# Power_Supply_Board.net
KiCad netlist of a schematic drawn in EAGLE
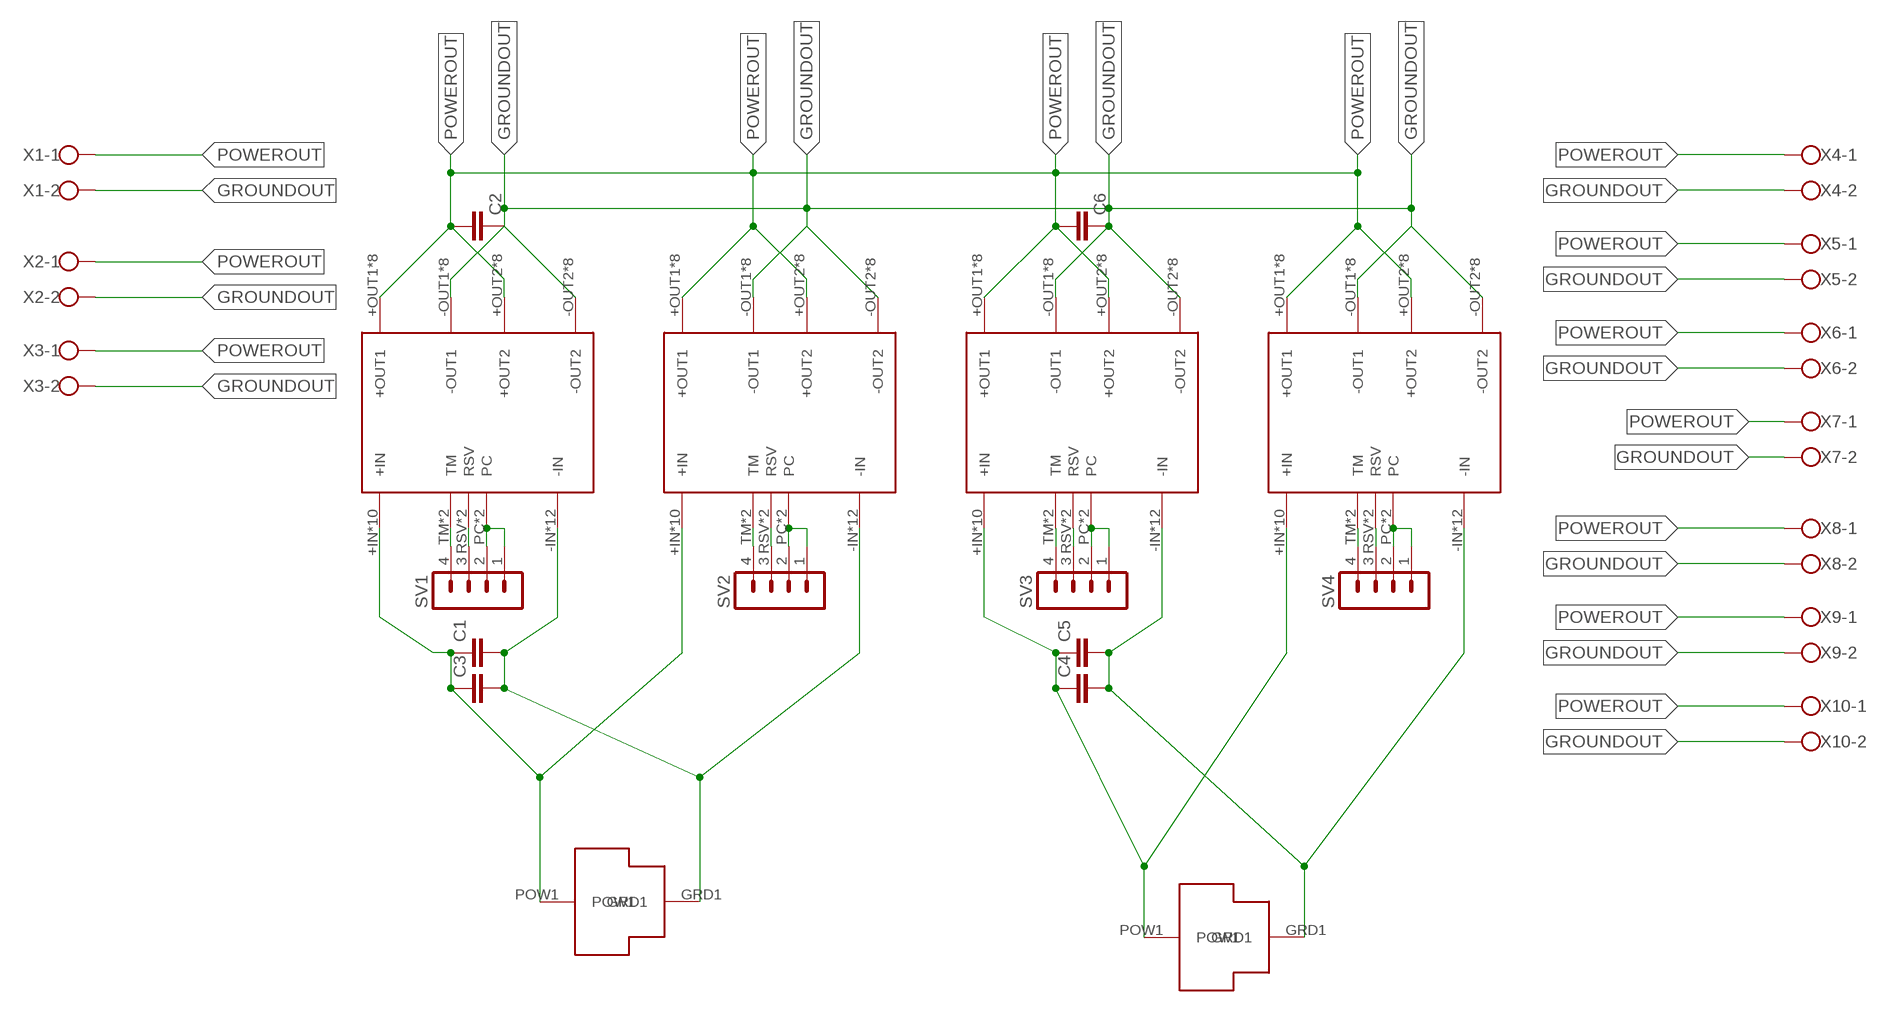
[diagram p0: schematic, sheet 1]

(export (version "E")
  (design (tool "Eeschema 10.0.6"))
  (components
    (comp (ref "C1")
      (value "C2,5-3")
      (footprint "eagle-import:C2.5-3")
      (libsource (lib "eagle-import") (part "C2,5-3"))
    )
    (comp (ref "C2")
      (value "C2,5-3")
      (footprint "eagle-import:C2.5-3")
      (libsource (lib "eagle-import") (part "C2,5-3"))
    )
    (comp (ref "C3")
      (value "C2,5-3")
      (footprint "eagle-import:C2.5-3")
      (libsource (lib "eagle-import") (part "C2,5-3"))
    )
    (comp (ref "C4")
      (value "C2,5-3")
      (footprint "eagle-import:C2.5-3")
      (libsource (lib "eagle-import") (part "C2,5-3"))
    )
    (comp (ref "C5")
      (value "C2,5-3")
      (footprint "eagle-import:C2.5-3")
      (libsource (lib "eagle-import") (part "C2,5-3"))
    )
    (comp (ref "C6")
      (value "C2,5-3")
      (footprint "eagle-import:C2.5-3")
      (libsource (lib "eagle-import") (part "C2,5-3"))
    )
    (comp (ref "SV1")
      (value "MA04-1")
      (footprint "eagle-import:MA04-1")
      (libsource (lib "eagle-import") (part "MA04-1"))
    )
    (comp (ref "SV2")
      (value "MA04-1")
      (footprint "eagle-import:MA04-1")
      (libsource (lib "eagle-import") (part "MA04-1"))
    )
    (comp (ref "SV3")
      (value "MA04-1")
      (footprint "eagle-import:MA04-1")
      (libsource (lib "eagle-import") (part "MA04-1"))
    )
    (comp (ref "SV4")
      (value "MA04-1")
      (footprint "eagle-import:MA04-1")
      (libsource (lib "eagle-import") (part "MA04-1"))
    )
    (comp (ref "U$3")
      (value "MOLEXMEGAFIT")
      (footprint "eagle-import:MOLEXMEGAFIT")
      (libsource (lib "eagle-import") (part "MOLEXMEGAFIT"))
    )
    (comp (ref "U$9")
      (value "MOLEXMEGAFIT")
      (footprint "eagle-import:MOLEXMEGAFIT")
      (libsource (lib "eagle-import") (part "MOLEXMEGAFIT"))
    )
    (comp (ref "VC1")
      (value "VOLTAGECONVERTER")
      (footprint "eagle-import:VOLTAGECONVERTER")
      (libsource (lib "eagle-import") (part "VOLTAGECONVERTER"))
    )
    (comp (ref "VC2")
      (value "VOLTAGECONVERTER")
      (footprint "eagle-import:VOLTAGECONVERTER")
      (libsource (lib "eagle-import") (part "VOLTAGECONVERTER"))
    )
    (comp (ref "VC3")
      (value "VOLTAGECONVERTER")
      (footprint "eagle-import:VOLTAGECONVERTER")
      (libsource (lib "eagle-import") (part "VOLTAGECONVERTER"))
    )
    (comp (ref "VC4")
      (value "VOLTAGECONVERTER")
      (footprint "eagle-import:VOLTAGECONVERTER")
      (libsource (lib "eagle-import") (part "VOLTAGECONVERTER"))
    )
    (comp (ref "X1")
      (value "W237-102")
      (footprint "eagle-import:W237-102")
      (fields (field (name "MPN") "237-102"))
      (libsource (lib "eagle-import") (part "W237-102"))
    )
    (comp (ref "X2")
      (value "W237-102")
      (footprint "eagle-import:W237-102")
      (fields (field (name "MPN") "237-102"))
      (libsource (lib "eagle-import") (part "W237-102"))
    )
    (comp (ref "X3")
      (value "W237-102")
      (footprint "eagle-import:W237-102")
      (fields (field (name "MPN") "237-102"))
      (libsource (lib "eagle-import") (part "W237-102"))
    )
    (comp (ref "X4")
      (value "W237-102")
      (footprint "eagle-import:W237-102")
      (fields (field (name "MPN") "237-102"))
      (libsource (lib "eagle-import") (part "W237-102"))
    )
    (comp (ref "X5")
      (value "W237-102")
      (footprint "eagle-import:W237-102")
      (fields (field (name "MPN") "237-102"))
      (libsource (lib "eagle-import") (part "W237-102"))
    )
    (comp (ref "X6")
      (value "W237-102")
      (footprint "eagle-import:W237-102")
      (fields (field (name "MPN") "237-102"))
      (libsource (lib "eagle-import") (part "W237-102"))
    )
    (comp (ref "X7")
      (value "W237-102")
      (footprint "eagle-import:W237-102")
      (fields (field (name "MPN") "237-102"))
      (libsource (lib "eagle-import") (part "W237-102"))
    )
    (comp (ref "X8")
      (value "W237-102")
      (footprint "eagle-import:W237-102")
      (fields (field (name "MPN") "237-102"))
      (libsource (lib "eagle-import") (part "W237-102"))
    )
    (comp (ref "X9")
      (value "W237-102")
      (footprint "eagle-import:W237-102")
      (fields (field (name "MPN") "237-102"))
      (libsource (lib "eagle-import") (part "W237-102"))
    )
    (comp (ref "X10")
      (value "W237-102")
      (footprint "eagle-import:W237-102")
      (fields (field (name "MPN") "237-102"))
      (libsource (lib "eagle-import") (part "W237-102"))
    )
  )
  (nets
    (net (code "1") (name "/GROUNDIN") (class "Default")
      (node (ref "C1") (pin "2") (pinfunction "2_2") (pintype "passive"))
      (node (ref "C3") (pin "2") (pinfunction "2_2") (pintype "passive"))
      (node (ref "C4") (pin "2") (pinfunction "2_2") (pintype "passive"))
      (node (ref "C5") (pin "2") (pinfunction "2_2") (pintype "passive"))
      (node (ref "U$3") (pin "GRD1") (pinfunction "GRD1_GRD1") (pintype "bidirectional"))
      (node (ref "U$9") (pin "GRD1") (pinfunction "GRD1_GRD1") (pintype "bidirectional"))
      (node (ref "VC1") (pin "-IN") (pinfunction "-IN_-IN") (pintype "bidirectional"))
      (node (ref "VC1") (pin "-IN@0") (pinfunction "-IN_-IN@0") (pintype "bidirectional"))
      (node (ref "VC1") (pin "-IN@1") (pinfunction "-IN_-IN@1") (pintype "bidirectional"))
      (node (ref "VC1") (pin "-IN@10") (pinfunction "-IN_-IN@10") (pintype "bidirectional"))
      (node (ref "VC1") (pin "-IN@2") (pinfunction "-IN_-IN@2") (pintype "bidirectional"))
      (node (ref "VC1") (pin "-IN@3") (pinfunction "-IN_-IN@3") (pintype "bidirectional"))
      (node (ref "VC1") (pin "-IN@4") (pinfunction "-IN_-IN@4") (pintype "bidirectional"))
      (node (ref "VC1") (pin "-IN@5") (pinfunction "-IN_-IN@5") (pintype "bidirectional"))
      (node (ref "VC1") (pin "-IN@6") (pinfunction "-IN_-IN@6") (pintype "bidirectional"))
      (node (ref "VC1") (pin "-IN@7") (pinfunction "-IN_-IN@7") (pintype "bidirectional"))
      (node (ref "VC1") (pin "-IN@8") (pinfunction "-IN_-IN@8") (pintype "bidirectional"))
      (node (ref "VC1") (pin "-IN@9") (pinfunction "-IN_-IN@9") (pintype "bidirectional"))
      (node (ref "VC2") (pin "-IN") (pinfunction "-IN_-IN") (pintype "bidirectional"))
      (node (ref "VC2") (pin "-IN@0") (pinfunction "-IN_-IN@0") (pintype "bidirectional"))
      (node (ref "VC2") (pin "-IN@1") (pinfunction "-IN_-IN@1") (pintype "bidirectional"))
      (node (ref "VC2") (pin "-IN@10") (pinfunction "-IN_-IN@10") (pintype "bidirectional"))
      (node (ref "VC2") (pin "-IN@2") (pinfunction "-IN_-IN@2") (pintype "bidirectional"))
      (node (ref "VC2") (pin "-IN@3") (pinfunction "-IN_-IN@3") (pintype "bidirectional"))
      (node (ref "VC2") (pin "-IN@4") (pinfunction "-IN_-IN@4") (pintype "bidirectional"))
      (node (ref "VC2") (pin "-IN@5") (pinfunction "-IN_-IN@5") (pintype "bidirectional"))
      (node (ref "VC2") (pin "-IN@6") (pinfunction "-IN_-IN@6") (pintype "bidirectional"))
      (node (ref "VC2") (pin "-IN@7") (pinfunction "-IN_-IN@7") (pintype "bidirectional"))
      (node (ref "VC2") (pin "-IN@8") (pinfunction "-IN_-IN@8") (pintype "bidirectional"))
      (node (ref "VC2") (pin "-IN@9") (pinfunction "-IN_-IN@9") (pintype "bidirectional"))
      (node (ref "VC3") (pin "-IN") (pinfunction "-IN_-IN") (pintype "bidirectional"))
      (node (ref "VC3") (pin "-IN@0") (pinfunction "-IN_-IN@0") (pintype "bidirectional"))
      (node (ref "VC3") (pin "-IN@1") (pinfunction "-IN_-IN@1") (pintype "bidirectional"))
      (node (ref "VC3") (pin "-IN@10") (pinfunction "-IN_-IN@10") (pintype "bidirectional"))
      (node (ref "VC3") (pin "-IN@2") (pinfunction "-IN_-IN@2") (pintype "bidirectional"))
      (node (ref "VC3") (pin "-IN@3") (pinfunction "-IN_-IN@3") (pintype "bidirectional"))
      (node (ref "VC3") (pin "-IN@4") (pinfunction "-IN_-IN@4") (pintype "bidirectional"))
      (node (ref "VC3") (pin "-IN@5") (pinfunction "-IN_-IN@5") (pintype "bidirectional"))
      (node (ref "VC3") (pin "-IN@6") (pinfunction "-IN_-IN@6") (pintype "bidirectional"))
      (node (ref "VC3") (pin "-IN@7") (pinfunction "-IN_-IN@7") (pintype "bidirectional"))
      (node (ref "VC3") (pin "-IN@8") (pinfunction "-IN_-IN@8") (pintype "bidirectional"))
      (node (ref "VC3") (pin "-IN@9") (pinfunction "-IN_-IN@9") (pintype "bidirectional"))
      (node (ref "VC4") (pin "-IN") (pinfunction "-IN_-IN") (pintype "bidirectional"))
      (node (ref "VC4") (pin "-IN@0") (pinfunction "-IN_-IN@0") (pintype "bidirectional"))
      (node (ref "VC4") (pin "-IN@1") (pinfunction "-IN_-IN@1") (pintype "bidirectional"))
      (node (ref "VC4") (pin "-IN@10") (pinfunction "-IN_-IN@10") (pintype "bidirectional"))
      (node (ref "VC4") (pin "-IN@2") (pinfunction "-IN_-IN@2") (pintype "bidirectional"))
      (node (ref "VC4") (pin "-IN@3") (pinfunction "-IN_-IN@3") (pintype "bidirectional"))
      (node (ref "VC4") (pin "-IN@4") (pinfunction "-IN_-IN@4") (pintype "bidirectional"))
      (node (ref "VC4") (pin "-IN@5") (pinfunction "-IN_-IN@5") (pintype "bidirectional"))
      (node (ref "VC4") (pin "-IN@6") (pinfunction "-IN_-IN@6") (pintype "bidirectional"))
      (node (ref "VC4") (pin "-IN@7") (pinfunction "-IN_-IN@7") (pintype "bidirectional"))
      (node (ref "VC4") (pin "-IN@8") (pinfunction "-IN_-IN@8") (pintype "bidirectional"))
      (node (ref "VC4") (pin "-IN@9") (pinfunction "-IN_-IN@9") (pintype "bidirectional"))
    )
    (net (code "2") (name "GROUNDOUT") (class "Default")
      (node (ref "C2") (pin "1") (pinfunction "1_1") (pintype "passive"))
      (node (ref "C6") (pin "1") (pinfunction "1_1") (pintype "passive"))
      (node (ref "VC1") (pin "-OUT1") (pinfunction "-OUT1_-OUT1") (pintype "bidirectional"))
      (node (ref "VC1") (pin "-OUT1@1") (pinfunction "-OUT1_-OUT1@1") (pintype "bidirectional"))
      (node (ref "VC1") (pin "-OUT1@2") (pinfunction "-OUT1_-OUT1@2") (pintype "bidirectional"))
      (node (ref "VC1") (pin "-OUT1@3") (pinfunction "-OUT1_-OUT1@3") (pintype "bidirectional"))
      (node (ref "VC1") (pin "-OUT1@4") (pinfunction "-OUT1_-OUT1@4") (pintype "bidirectional"))
      (node (ref "VC1") (pin "-OUT1@5") (pinfunction "-OUT1_-OUT1@5") (pintype "bidirectional"))
      (node (ref "VC1") (pin "-OUT1@6") (pinfunction "-OUT1_-OUT1@6") (pintype "bidirectional"))
      (node (ref "VC1") (pin "-OUT1@7") (pinfunction "-OUT1_-OUT1@7") (pintype "bidirectional"))
      (node (ref "VC1") (pin "-OUT2") (pinfunction "-OUT2_-OUT2") (pintype "bidirectional"))
      (node (ref "VC1") (pin "-OUT2@1") (pinfunction "-OUT2_-OUT2@1") (pintype "bidirectional"))
      (node (ref "VC1") (pin "-OUT2@2") (pinfunction "-OUT2_-OUT2@2") (pintype "bidirectional"))
      (node (ref "VC1") (pin "-OUT2@3") (pinfunction "-OUT2_-OUT2@3") (pintype "bidirectional"))
      (node (ref "VC1") (pin "-OUT2@4") (pinfunction "-OUT2_-OUT2@4") (pintype "bidirectional"))
      (node (ref "VC1") (pin "-OUT2@5") (pinfunction "-OUT2_-OUT2@5") (pintype "bidirectional"))
      (node (ref "VC1") (pin "-OUT2@6") (pinfunction "-OUT2_-OUT2@6") (pintype "bidirectional"))
      (node (ref "VC1") (pin "-OUT2@7") (pinfunction "-OUT2_-OUT2@7") (pintype "bidirectional"))
      (node (ref "VC2") (pin "-OUT1") (pinfunction "-OUT1_-OUT1") (pintype "bidirectional"))
      (node (ref "VC2") (pin "-OUT1@1") (pinfunction "-OUT1_-OUT1@1") (pintype "bidirectional"))
      (node (ref "VC2") (pin "-OUT1@2") (pinfunction "-OUT1_-OUT1@2") (pintype "bidirectional"))
      (node (ref "VC2") (pin "-OUT1@3") (pinfunction "-OUT1_-OUT1@3") (pintype "bidirectional"))
      (node (ref "VC2") (pin "-OUT1@4") (pinfunction "-OUT1_-OUT1@4") (pintype "bidirectional"))
      (node (ref "VC2") (pin "-OUT1@5") (pinfunction "-OUT1_-OUT1@5") (pintype "bidirectional"))
      (node (ref "VC2") (pin "-OUT1@6") (pinfunction "-OUT1_-OUT1@6") (pintype "bidirectional"))
      (node (ref "VC2") (pin "-OUT1@7") (pinfunction "-OUT1_-OUT1@7") (pintype "bidirectional"))
      (node (ref "VC2") (pin "-OUT2") (pinfunction "-OUT2_-OUT2") (pintype "bidirectional"))
      (node (ref "VC2") (pin "-OUT2@1") (pinfunction "-OUT2_-OUT2@1") (pintype "bidirectional"))
      (node (ref "VC2") (pin "-OUT2@2") (pinfunction "-OUT2_-OUT2@2") (pintype "bidirectional"))
      (node (ref "VC2") (pin "-OUT2@3") (pinfunction "-OUT2_-OUT2@3") (pintype "bidirectional"))
      (node (ref "VC2") (pin "-OUT2@4") (pinfunction "-OUT2_-OUT2@4") (pintype "bidirectional"))
      (node (ref "VC2") (pin "-OUT2@5") (pinfunction "-OUT2_-OUT2@5") (pintype "bidirectional"))
      (node (ref "VC2") (pin "-OUT2@6") (pinfunction "-OUT2_-OUT2@6") (pintype "bidirectional"))
      (node (ref "VC2") (pin "-OUT2@7") (pinfunction "-OUT2_-OUT2@7") (pintype "bidirectional"))
      (node (ref "VC3") (pin "-OUT1") (pinfunction "-OUT1_-OUT1") (pintype "bidirectional"))
      (node (ref "VC3") (pin "-OUT1@1") (pinfunction "-OUT1_-OUT1@1") (pintype "bidirectional"))
      (node (ref "VC3") (pin "-OUT1@2") (pinfunction "-OUT1_-OUT1@2") (pintype "bidirectional"))
      (node (ref "VC3") (pin "-OUT1@3") (pinfunction "-OUT1_-OUT1@3") (pintype "bidirectional"))
      (node (ref "VC3") (pin "-OUT1@4") (pinfunction "-OUT1_-OUT1@4") (pintype "bidirectional"))
      (node (ref "VC3") (pin "-OUT1@5") (pinfunction "-OUT1_-OUT1@5") (pintype "bidirectional"))
      (node (ref "VC3") (pin "-OUT1@6") (pinfunction "-OUT1_-OUT1@6") (pintype "bidirectional"))
      (node (ref "VC3") (pin "-OUT1@7") (pinfunction "-OUT1_-OUT1@7") (pintype "bidirectional"))
      (node (ref "VC3") (pin "-OUT2") (pinfunction "-OUT2_-OUT2") (pintype "bidirectional"))
      (node (ref "VC3") (pin "-OUT2@1") (pinfunction "-OUT2_-OUT2@1") (pintype "bidirectional"))
      (node (ref "VC3") (pin "-OUT2@2") (pinfunction "-OUT2_-OUT2@2") (pintype "bidirectional"))
      (node (ref "VC3") (pin "-OUT2@3") (pinfunction "-OUT2_-OUT2@3") (pintype "bidirectional"))
      (node (ref "VC3") (pin "-OUT2@4") (pinfunction "-OUT2_-OUT2@4") (pintype "bidirectional"))
      (node (ref "VC3") (pin "-OUT2@5") (pinfunction "-OUT2_-OUT2@5") (pintype "bidirectional"))
      (node (ref "VC3") (pin "-OUT2@6") (pinfunction "-OUT2_-OUT2@6") (pintype "bidirectional"))
      (node (ref "VC3") (pin "-OUT2@7") (pinfunction "-OUT2_-OUT2@7") (pintype "bidirectional"))
      (node (ref "VC4") (pin "-OUT1") (pinfunction "-OUT1_-OUT1") (pintype "bidirectional"))
      (node (ref "VC4") (pin "-OUT1@1") (pinfunction "-OUT1_-OUT1@1") (pintype "bidirectional"))
      (node (ref "VC4") (pin "-OUT1@2") (pinfunction "-OUT1_-OUT1@2") (pintype "bidirectional"))
      (node (ref "VC4") (pin "-OUT1@3") (pinfunction "-OUT1_-OUT1@3") (pintype "bidirectional"))
      (node (ref "VC4") (pin "-OUT1@4") (pinfunction "-OUT1_-OUT1@4") (pintype "bidirectional"))
      (node (ref "VC4") (pin "-OUT1@5") (pinfunction "-OUT1_-OUT1@5") (pintype "bidirectional"))
      (node (ref "VC4") (pin "-OUT1@6") (pinfunction "-OUT1_-OUT1@6") (pintype "bidirectional"))
      (node (ref "VC4") (pin "-OUT1@7") (pinfunction "-OUT1_-OUT1@7") (pintype "bidirectional"))
      (node (ref "VC4") (pin "-OUT2") (pinfunction "-OUT2_-OUT2") (pintype "bidirectional"))
      (node (ref "VC4") (pin "-OUT2@1") (pinfunction "-OUT2_-OUT2@1") (pintype "bidirectional"))
      (node (ref "VC4") (pin "-OUT2@2") (pinfunction "-OUT2_-OUT2@2") (pintype "bidirectional"))
      (node (ref "VC4") (pin "-OUT2@3") (pinfunction "-OUT2_-OUT2@3") (pintype "bidirectional"))
      (node (ref "VC4") (pin "-OUT2@4") (pinfunction "-OUT2_-OUT2@4") (pintype "bidirectional"))
      (node (ref "VC4") (pin "-OUT2@5") (pinfunction "-OUT2_-OUT2@5") (pintype "bidirectional"))
      (node (ref "VC4") (pin "-OUT2@6") (pinfunction "-OUT2_-OUT2@6") (pintype "bidirectional"))
      (node (ref "VC4") (pin "-OUT2@7") (pinfunction "-OUT2_-OUT2@7") (pintype "bidirectional"))
      (node (ref "X1") (pin "2") (pinfunction "KL_2") (pintype "passive"))
      (node (ref "X10") (pin "2") (pinfunction "KL_2") (pintype "passive"))
      (node (ref "X2") (pin "2") (pinfunction "KL_2") (pintype "passive"))
      (node (ref "X3") (pin "2") (pinfunction "KL_2") (pintype "passive"))
      (node (ref "X4") (pin "2") (pinfunction "KL_2") (pintype "passive"))
      (node (ref "X5") (pin "2") (pinfunction "KL_2") (pintype "passive"))
      (node (ref "X6") (pin "2") (pinfunction "KL_2") (pintype "passive"))
      (node (ref "X7") (pin "2") (pinfunction "KL_2") (pintype "passive"))
      (node (ref "X8") (pin "2") (pinfunction "KL_2") (pintype "passive"))
      (node (ref "X9") (pin "2") (pinfunction "KL_2") (pintype "passive"))
    )
    (net (code "3") (name "Net-(C1-Pad1)") (class "Default")
      (node (ref "C1") (pin "1") (pinfunction "1_1") (pintype "passive"))
      (node (ref "C3") (pin "1") (pinfunction "1_1") (pintype "passive"))
      (node (ref "U$3") (pin "POW1") (pinfunction "POW1_POW1") (pintype "bidirectional"))
      (node (ref "VC1") (pin "+IN") (pinfunction "+IN_+IN") (pintype "bidirectional"))
      (node (ref "VC1") (pin "+IN@1") (pinfunction "+IN_+IN@1") (pintype "bidirectional"))
      (node (ref "VC1") (pin "+IN@2") (pinfunction "+IN_+IN@2") (pintype "bidirectional"))
      (node (ref "VC1") (pin "+IN@3") (pinfunction "+IN_+IN@3") (pintype "bidirectional"))
      (node (ref "VC1") (pin "+IN@4") (pinfunction "+IN_+IN@4") (pintype "bidirectional"))
      (node (ref "VC1") (pin "+IN@5") (pinfunction "+IN_+IN@5") (pintype "bidirectional"))
      (node (ref "VC1") (pin "+IN@6") (pinfunction "+IN_+IN@6") (pintype "bidirectional"))
      (node (ref "VC1") (pin "+IN@7") (pinfunction "+IN_+IN@7") (pintype "bidirectional"))
      (node (ref "VC1") (pin "+IN@8") (pinfunction "+IN_+IN@8") (pintype "bidirectional"))
      (node (ref "VC1") (pin "+IN@9") (pinfunction "+IN_+IN@9") (pintype "bidirectional"))
      (node (ref "VC2") (pin "+IN") (pinfunction "+IN_+IN") (pintype "bidirectional"))
      (node (ref "VC2") (pin "+IN@1") (pinfunction "+IN_+IN@1") (pintype "bidirectional"))
      (node (ref "VC2") (pin "+IN@2") (pinfunction "+IN_+IN@2") (pintype "bidirectional"))
      (node (ref "VC2") (pin "+IN@3") (pinfunction "+IN_+IN@3") (pintype "bidirectional"))
      (node (ref "VC2") (pin "+IN@4") (pinfunction "+IN_+IN@4") (pintype "bidirectional"))
      (node (ref "VC2") (pin "+IN@5") (pinfunction "+IN_+IN@5") (pintype "bidirectional"))
      (node (ref "VC2") (pin "+IN@6") (pinfunction "+IN_+IN@6") (pintype "bidirectional"))
      (node (ref "VC2") (pin "+IN@7") (pinfunction "+IN_+IN@7") (pintype "bidirectional"))
      (node (ref "VC2") (pin "+IN@8") (pinfunction "+IN_+IN@8") (pintype "bidirectional"))
      (node (ref "VC2") (pin "+IN@9") (pinfunction "+IN_+IN@9") (pintype "bidirectional"))
    )
    (net (code "4") (name "Net-(C4-Pad1)") (class "Default")
      (node (ref "C4") (pin "1") (pinfunction "1_1") (pintype "passive"))
      (node (ref "C5") (pin "1") (pinfunction "1_1") (pintype "passive"))
      (node (ref "U$9") (pin "POW1") (pinfunction "POW1_POW1") (pintype "bidirectional"))
      (node (ref "VC3") (pin "+IN") (pinfunction "+IN_+IN") (pintype "bidirectional"))
      (node (ref "VC3") (pin "+IN@1") (pinfunction "+IN_+IN@1") (pintype "bidirectional"))
      (node (ref "VC3") (pin "+IN@2") (pinfunction "+IN_+IN@2") (pintype "bidirectional"))
      (node (ref "VC3") (pin "+IN@3") (pinfunction "+IN_+IN@3") (pintype "bidirectional"))
      (node (ref "VC3") (pin "+IN@4") (pinfunction "+IN_+IN@4") (pintype "bidirectional"))
      (node (ref "VC3") (pin "+IN@5") (pinfunction "+IN_+IN@5") (pintype "bidirectional"))
      (node (ref "VC3") (pin "+IN@6") (pinfunction "+IN_+IN@6") (pintype "bidirectional"))
      (node (ref "VC3") (pin "+IN@7") (pinfunction "+IN_+IN@7") (pintype "bidirectional"))
      (node (ref "VC3") (pin "+IN@8") (pinfunction "+IN_+IN@8") (pintype "bidirectional"))
      (node (ref "VC3") (pin "+IN@9") (pinfunction "+IN_+IN@9") (pintype "bidirectional"))
      (node (ref "VC4") (pin "+IN") (pinfunction "+IN_+IN") (pintype "bidirectional"))
      (node (ref "VC4") (pin "+IN@1") (pinfunction "+IN_+IN@1") (pintype "bidirectional"))
      (node (ref "VC4") (pin "+IN@2") (pinfunction "+IN_+IN@2") (pintype "bidirectional"))
      (node (ref "VC4") (pin "+IN@3") (pinfunction "+IN_+IN@3") (pintype "bidirectional"))
      (node (ref "VC4") (pin "+IN@4") (pinfunction "+IN_+IN@4") (pintype "bidirectional"))
      (node (ref "VC4") (pin "+IN@5") (pinfunction "+IN_+IN@5") (pintype "bidirectional"))
      (node (ref "VC4") (pin "+IN@6") (pinfunction "+IN_+IN@6") (pintype "bidirectional"))
      (node (ref "VC4") (pin "+IN@7") (pinfunction "+IN_+IN@7") (pintype "bidirectional"))
      (node (ref "VC4") (pin "+IN@8") (pinfunction "+IN_+IN@8") (pintype "bidirectional"))
      (node (ref "VC4") (pin "+IN@9") (pinfunction "+IN_+IN@9") (pintype "bidirectional"))
    )
    (net (code "5") (name "Net-(SV1-Pad1)") (class "Default")
      (node (ref "SV1") (pin "1") (pinfunction "1_1") (pintype "passive"))
      (node (ref "SV1") (pin "2") (pinfunction "2_2") (pintype "passive"))
      (node (ref "VC1") (pin "PC") (pinfunction "PC_PC") (pintype "bidirectional"))
      (node (ref "VC1") (pin "PC21") (pinfunction "PC_PC21") (pintype "bidirectional"))
    )
    (net (code "6") (name "Net-(SV1-Pad3)") (class "Default")
      (node (ref "SV1") (pin "3") (pinfunction "3_3") (pintype "passive"))
      (node (ref "VC1") (pin "RSV") (pinfunction "RSV_RSV") (pintype "bidirectional"))
      (node (ref "VC1") (pin "RSV@1") (pinfunction "RSV_RSV@1") (pintype "bidirectional"))
    )
    (net (code "7") (name "Net-(SV1-Pad4)") (class "Default")
      (node (ref "SV1") (pin "4") (pinfunction "4_4") (pintype "passive"))
      (node (ref "VC1") (pin "TM") (pinfunction "TM_TM") (pintype "bidirectional"))
      (node (ref "VC1") (pin "TM@1") (pinfunction "TM_TM@1") (pintype "bidirectional"))
    )
    (net (code "8") (name "Net-(SV2-Pad1)") (class "Default")
      (node (ref "SV2") (pin "1") (pinfunction "1_1") (pintype "passive"))
      (node (ref "SV2") (pin "2") (pinfunction "2_2") (pintype "passive"))
      (node (ref "VC2") (pin "PC") (pinfunction "PC_PC") (pintype "bidirectional"))
      (node (ref "VC2") (pin "PC21") (pinfunction "PC_PC21") (pintype "bidirectional"))
    )
    (net (code "9") (name "Net-(SV2-Pad3)") (class "Default")
      (node (ref "SV2") (pin "3") (pinfunction "3_3") (pintype "passive"))
      (node (ref "VC2") (pin "RSV") (pinfunction "RSV_RSV") (pintype "bidirectional"))
      (node (ref "VC2") (pin "RSV@1") (pinfunction "RSV_RSV@1") (pintype "bidirectional"))
    )
    (net (code "10") (name "Net-(SV2-Pad4)") (class "Default")
      (node (ref "SV2") (pin "4") (pinfunction "4_4") (pintype "passive"))
      (node (ref "VC2") (pin "TM") (pinfunction "TM_TM") (pintype "bidirectional"))
      (node (ref "VC2") (pin "TM@1") (pinfunction "TM_TM@1") (pintype "bidirectional"))
    )
    (net (code "11") (name "Net-(SV3-Pad1)") (class "Default")
      (node (ref "SV3") (pin "1") (pinfunction "1_1") (pintype "passive"))
      (node (ref "SV3") (pin "2") (pinfunction "2_2") (pintype "passive"))
      (node (ref "VC3") (pin "PC") (pinfunction "PC_PC") (pintype "bidirectional"))
      (node (ref "VC3") (pin "PC21") (pinfunction "PC_PC21") (pintype "bidirectional"))
    )
    (net (code "12") (name "Net-(SV3-Pad3)") (class "Default")
      (node (ref "SV3") (pin "3") (pinfunction "3_3") (pintype "passive"))
      (node (ref "VC3") (pin "RSV") (pinfunction "RSV_RSV") (pintype "bidirectional"))
      (node (ref "VC3") (pin "RSV@1") (pinfunction "RSV_RSV@1") (pintype "bidirectional"))
    )
    (net (code "13") (name "Net-(SV3-Pad4)") (class "Default")
      (node (ref "SV3") (pin "4") (pinfunction "4_4") (pintype "passive"))
      (node (ref "VC3") (pin "TM") (pinfunction "TM_TM") (pintype "bidirectional"))
      (node (ref "VC3") (pin "TM@1") (pinfunction "TM_TM@1") (pintype "bidirectional"))
    )
    (net (code "14") (name "Net-(SV4-Pad1)") (class "Default")
      (node (ref "SV4") (pin "1") (pinfunction "1_1") (pintype "passive"))
      (node (ref "SV4") (pin "2") (pinfunction "2_2") (pintype "passive"))
      (node (ref "VC4") (pin "PC") (pinfunction "PC_PC") (pintype "bidirectional"))
      (node (ref "VC4") (pin "PC21") (pinfunction "PC_PC21") (pintype "bidirectional"))
    )
    (net (code "15") (name "Net-(SV4-Pad3)") (class "Default")
      (node (ref "SV4") (pin "3") (pinfunction "3_3") (pintype "passive"))
      (node (ref "VC4") (pin "RSV") (pinfunction "RSV_RSV") (pintype "bidirectional"))
      (node (ref "VC4") (pin "RSV@1") (pinfunction "RSV_RSV@1") (pintype "bidirectional"))
    )
    (net (code "16") (name "Net-(SV4-Pad4)") (class "Default")
      (node (ref "SV4") (pin "4") (pinfunction "4_4") (pintype "passive"))
      (node (ref "VC4") (pin "TM") (pinfunction "TM_TM") (pintype "bidirectional"))
      (node (ref "VC4") (pin "TM@1") (pinfunction "TM_TM@1") (pintype "bidirectional"))
    )
    (net (code "17") (name "POWEROUT") (class "Default")
      (node (ref "C2") (pin "2") (pinfunction "2_2") (pintype "passive"))
      (node (ref "C6") (pin "2") (pinfunction "2_2") (pintype "passive"))
      (node (ref "VC1") (pin "+OUT1") (pinfunction "+OUT1_+OUT1") (pintype "bidirectional"))
      (node (ref "VC1") (pin "+OUT1@1") (pinfunction "+OUT1_+OUT1@1") (pintype "bidirectional"))
      (node (ref "VC1") (pin "+OUT1@2") (pinfunction "+OUT1_+OUT1@2") (pintype "bidirectional"))
      (node (ref "VC1") (pin "+OUT1@3") (pinfunction "+OUT1_+OUT1@3") (pintype "bidirectional"))
      (node (ref "VC1") (pin "+OUT1@4") (pinfunction "+OUT1_+OUT1@4") (pintype "bidirectional"))
      (node (ref "VC1") (pin "+OUT1@5") (pinfunction "+OUT1_+OUT1@5") (pintype "bidirectional"))
      (node (ref "VC1") (pin "+OUT1@6") (pinfunction "+OUT1_+OUT1@6") (pintype "bidirectional"))
      (node (ref "VC1") (pin "+OUT1@7") (pinfunction "+OUT1_+OUT1@7") (pintype "bidirectional"))
      (node (ref "VC1") (pin "+OUT2") (pinfunction "+OUT2_+OUT2") (pintype "bidirectional"))
      (node (ref "VC1") (pin "+OUT2@1") (pinfunction "+OUT2_+OUT2@1") (pintype "bidirectional"))
      (node (ref "VC1") (pin "+OUT2@2") (pinfunction "+OUT2_+OUT2@2") (pintype "bidirectional"))
      (node (ref "VC1") (pin "+OUT2@3") (pinfunction "+OUT2_+OUT2@3") (pintype "bidirectional"))
      (node (ref "VC1") (pin "+OUT2@4") (pinfunction "+OUT2_+OUT2@4") (pintype "bidirectional"))
      (node (ref "VC1") (pin "+OUT2@5") (pinfunction "+OUT2_+OUT2@5") (pintype "bidirectional"))
      (node (ref "VC1") (pin "+OUT2@6") (pinfunction "+OUT2_+OUT2@6") (pintype "bidirectional"))
      (node (ref "VC1") (pin "+OUT2@7") (pinfunction "+OUT2_+OUT2@7") (pintype "bidirectional"))
      (node (ref "VC2") (pin "+OUT1") (pinfunction "+OUT1_+OUT1") (pintype "bidirectional"))
      (node (ref "VC2") (pin "+OUT1@1") (pinfunction "+OUT1_+OUT1@1") (pintype "bidirectional"))
      (node (ref "VC2") (pin "+OUT1@2") (pinfunction "+OUT1_+OUT1@2") (pintype "bidirectional"))
      (node (ref "VC2") (pin "+OUT1@3") (pinfunction "+OUT1_+OUT1@3") (pintype "bidirectional"))
      (node (ref "VC2") (pin "+OUT1@4") (pinfunction "+OUT1_+OUT1@4") (pintype "bidirectional"))
      (node (ref "VC2") (pin "+OUT1@5") (pinfunction "+OUT1_+OUT1@5") (pintype "bidirectional"))
      (node (ref "VC2") (pin "+OUT1@6") (pinfunction "+OUT1_+OUT1@6") (pintype "bidirectional"))
      (node (ref "VC2") (pin "+OUT1@7") (pinfunction "+OUT1_+OUT1@7") (pintype "bidirectional"))
      (node (ref "VC2") (pin "+OUT2") (pinfunction "+OUT2_+OUT2") (pintype "bidirectional"))
      (node (ref "VC2") (pin "+OUT2@1") (pinfunction "+OUT2_+OUT2@1") (pintype "bidirectional"))
      (node (ref "VC2") (pin "+OUT2@2") (pinfunction "+OUT2_+OUT2@2") (pintype "bidirectional"))
      (node (ref "VC2") (pin "+OUT2@3") (pinfunction "+OUT2_+OUT2@3") (pintype "bidirectional"))
      (node (ref "VC2") (pin "+OUT2@4") (pinfunction "+OUT2_+OUT2@4") (pintype "bidirectional"))
      (node (ref "VC2") (pin "+OUT2@5") (pinfunction "+OUT2_+OUT2@5") (pintype "bidirectional"))
      (node (ref "VC2") (pin "+OUT2@6") (pinfunction "+OUT2_+OUT2@6") (pintype "bidirectional"))
      (node (ref "VC2") (pin "+OUT2@7") (pinfunction "+OUT2_+OUT2@7") (pintype "bidirectional"))
      (node (ref "VC3") (pin "+OUT1") (pinfunction "+OUT1_+OUT1") (pintype "bidirectional"))
      (node (ref "VC3") (pin "+OUT1@1") (pinfunction "+OUT1_+OUT1@1") (pintype "bidirectional"))
      (node (ref "VC3") (pin "+OUT1@2") (pinfunction "+OUT1_+OUT1@2") (pintype "bidirectional"))
      (node (ref "VC3") (pin "+OUT1@3") (pinfunction "+OUT1_+OUT1@3") (pintype "bidirectional"))
      (node (ref "VC3") (pin "+OUT1@4") (pinfunction "+OUT1_+OUT1@4") (pintype "bidirectional"))
      (node (ref "VC3") (pin "+OUT1@5") (pinfunction "+OUT1_+OUT1@5") (pintype "bidirectional"))
      (node (ref "VC3") (pin "+OUT1@6") (pinfunction "+OUT1_+OUT1@6") (pintype "bidirectional"))
      (node (ref "VC3") (pin "+OUT1@7") (pinfunction "+OUT1_+OUT1@7") (pintype "bidirectional"))
      (node (ref "VC3") (pin "+OUT2") (pinfunction "+OUT2_+OUT2") (pintype "bidirectional"))
      (node (ref "VC3") (pin "+OUT2@1") (pinfunction "+OUT2_+OUT2@1") (pintype "bidirectional"))
      (node (ref "VC3") (pin "+OUT2@2") (pinfunction "+OUT2_+OUT2@2") (pintype "bidirectional"))
      (node (ref "VC3") (pin "+OUT2@3") (pinfunction "+OUT2_+OUT2@3") (pintype "bidirectional"))
      (node (ref "VC3") (pin "+OUT2@4") (pinfunction "+OUT2_+OUT2@4") (pintype "bidirectional"))
      (node (ref "VC3") (pin "+OUT2@5") (pinfunction "+OUT2_+OUT2@5") (pintype "bidirectional"))
      (node (ref "VC3") (pin "+OUT2@6") (pinfunction "+OUT2_+OUT2@6") (pintype "bidirectional"))
      (node (ref "VC3") (pin "+OUT2@7") (pinfunction "+OUT2_+OUT2@7") (pintype "bidirectional"))
      (node (ref "VC4") (pin "+OUT1") (pinfunction "+OUT1_+OUT1") (pintype "bidirectional"))
      (node (ref "VC4") (pin "+OUT1@1") (pinfunction "+OUT1_+OUT1@1") (pintype "bidirectional"))
      (node (ref "VC4") (pin "+OUT1@2") (pinfunction "+OUT1_+OUT1@2") (pintype "bidirectional"))
      (node (ref "VC4") (pin "+OUT1@3") (pinfunction "+OUT1_+OUT1@3") (pintype "bidirectional"))
      (node (ref "VC4") (pin "+OUT1@4") (pinfunction "+OUT1_+OUT1@4") (pintype "bidirectional"))
      (node (ref "VC4") (pin "+OUT1@5") (pinfunction "+OUT1_+OUT1@5") (pintype "bidirectional"))
      (node (ref "VC4") (pin "+OUT1@6") (pinfunction "+OUT1_+OUT1@6") (pintype "bidirectional"))
      (node (ref "VC4") (pin "+OUT1@7") (pinfunction "+OUT1_+OUT1@7") (pintype "bidirectional"))
      (node (ref "VC4") (pin "+OUT2") (pinfunction "+OUT2_+OUT2") (pintype "bidirectional"))
      (node (ref "VC4") (pin "+OUT2@1") (pinfunction "+OUT2_+OUT2@1") (pintype "bidirectional"))
      (node (ref "VC4") (pin "+OUT2@2") (pinfunction "+OUT2_+OUT2@2") (pintype "bidirectional"))
      (node (ref "VC4") (pin "+OUT2@3") (pinfunction "+OUT2_+OUT2@3") (pintype "bidirectional"))
      (node (ref "VC4") (pin "+OUT2@4") (pinfunction "+OUT2_+OUT2@4") (pintype "bidirectional"))
      (node (ref "VC4") (pin "+OUT2@5") (pinfunction "+OUT2_+OUT2@5") (pintype "bidirectional"))
      (node (ref "VC4") (pin "+OUT2@6") (pinfunction "+OUT2_+OUT2@6") (pintype "bidirectional"))
      (node (ref "VC4") (pin "+OUT2@7") (pinfunction "+OUT2_+OUT2@7") (pintype "bidirectional"))
      (node (ref "X1") (pin "1") (pinfunction "KL_1") (pintype "passive"))
      (node (ref "X10") (pin "1") (pinfunction "KL_1") (pintype "passive"))
      (node (ref "X2") (pin "1") (pinfunction "KL_1") (pintype "passive"))
      (node (ref "X3") (pin "1") (pinfunction "KL_1") (pintype "passive"))
      (node (ref "X4") (pin "1") (pinfunction "KL_1") (pintype "passive"))
      (node (ref "X5") (pin "1") (pinfunction "KL_1") (pintype "passive"))
      (node (ref "X6") (pin "1") (pinfunction "KL_1") (pintype "passive"))
      (node (ref "X7") (pin "1") (pinfunction "KL_1") (pintype "passive"))
      (node (ref "X8") (pin "1") (pinfunction "KL_1") (pintype "passive"))
      (node (ref "X9") (pin "1") (pinfunction "KL_1") (pintype "passive"))
    )
  )
)
